# DM1097_RIGHT_OV9282.net
KiCad netlist of a schematic drawn in Altium Designer
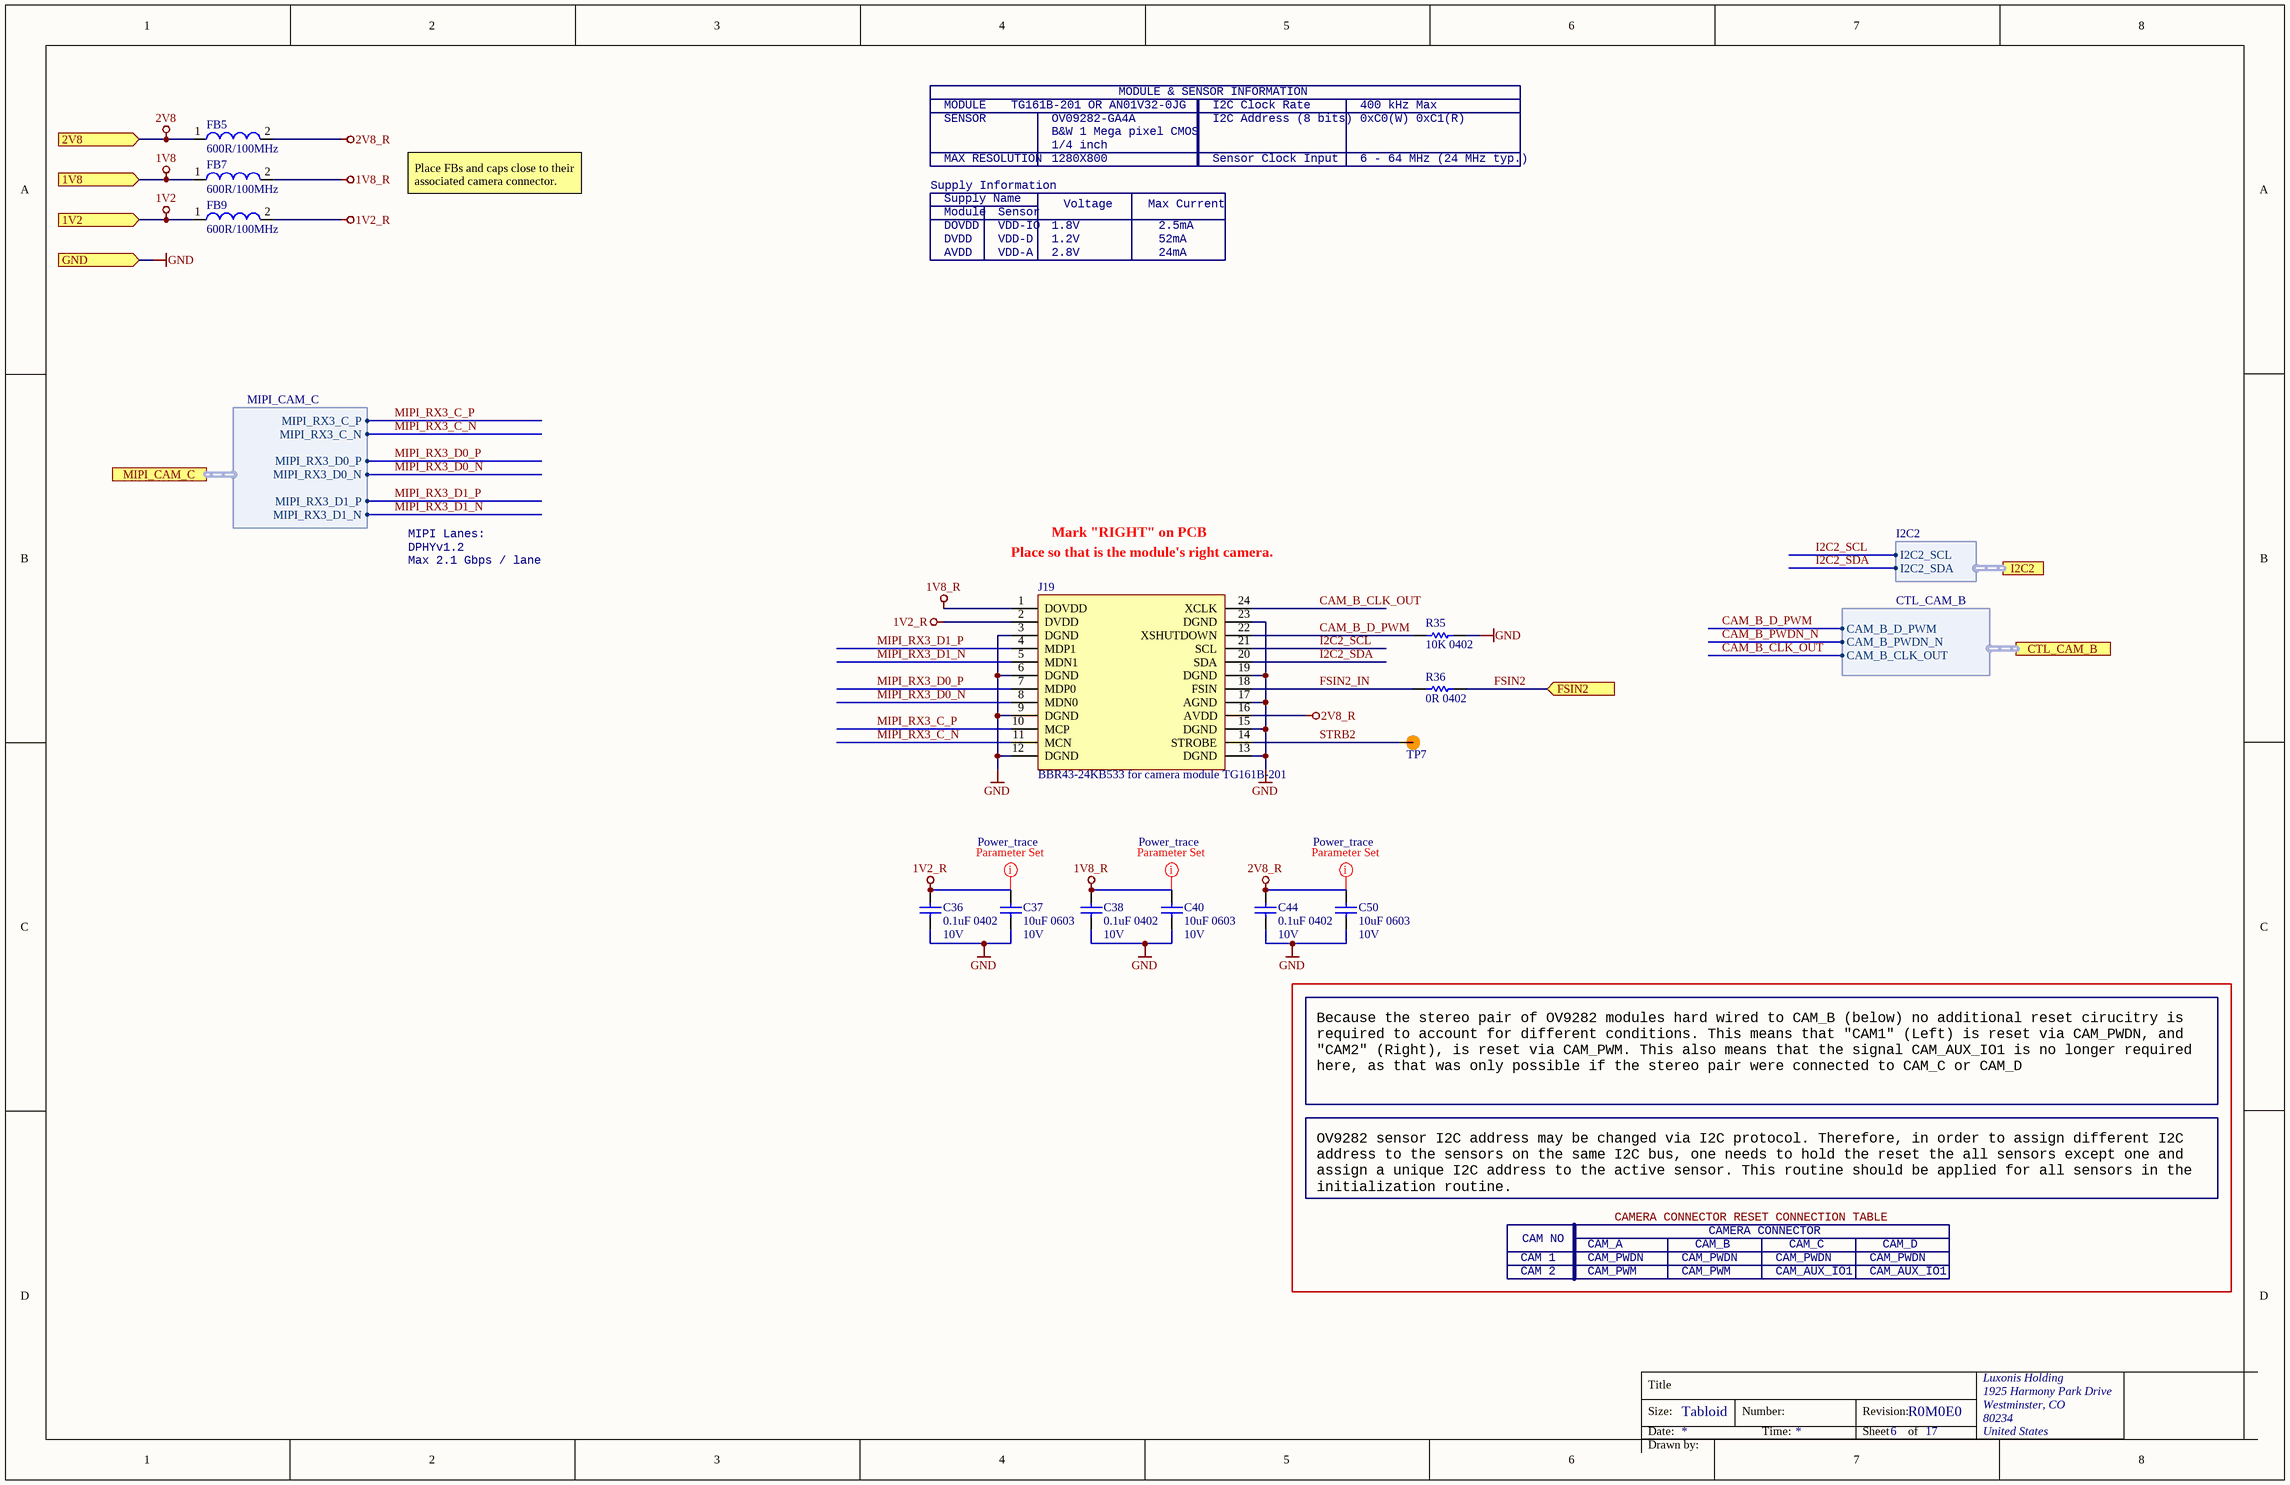
[diagram p0: DM1097_RIGHT_OV9282.SchDoc]

(export (version "E")
  (design (tool "Eeschema 10.0.6"))
  (components
    (comp (ref "C36")
      (value "0.1uF 0402")
      (footprint "CAP_Altium_Vault_Generic:CAPC0402(1005)70_N")
      (description "CAP CER 0.1UF 10V X7R 0402 5%")
      (fields (field (name "TOLERANCE") "5%") (field (name "VOLTAGE RATING") "10V"))
      (libsource (lib "LuxonisMaster") (part "GRM155R71A104JA01D"))
    )
    (comp (ref "C37")
      (value "10uF 0603")
      (footprint "CAP_Altium_Vault_Generic:CAPC0603(1608)100_N")
      (description "CAP CER 10UF 10V X5R 0603 20%")
      (fields (field (name "TOLERANCE") "20%") (field (name "VOLTAGE RATING") "10V"))
      (libsource (lib "LuxonisMaster") (part "GRM188R61A106ME69D"))
    )
    (comp (ref "C38")
      (value "0.1uF 0402")
      (footprint "CAP_Altium_Vault_Generic:CAPC0402(1005)70_N")
      (description "CAP CER 0.1UF 10V X7R 0402 5%")
      (fields (field (name "TOLERANCE") "5%") (field (name "VOLTAGE RATING") "10V"))
      (libsource (lib "LuxonisMaster") (part "GRM155R71A104JA01D"))
    )
    (comp (ref "C40")
      (value "10uF 0603")
      (footprint "CAP_Altium_Vault_Generic:CAPC0603(1608)100_N")
      (description "CAP CER 10UF 10V X5R 0603 20%")
      (fields (field (name "TOLERANCE") "20%") (field (name "VOLTAGE RATING") "10V"))
      (libsource (lib "LuxonisMaster") (part "GRM188R61A106ME69D"))
    )
    (comp (ref "C44")
      (value "0.1uF 0402")
      (footprint "CAP_Altium_Vault_Generic:CAPC0402(1005)70_N")
      (description "CAP CER 0.1UF 10V X7R 0402 5%")
      (fields (field (name "TOLERANCE") "5%") (field (name "VOLTAGE RATING") "10V"))
      (libsource (lib "LuxonisMaster") (part "GRM155R71A104JA01D"))
    )
    (comp (ref "C50")
      (value "10uF 0603")
      (footprint "CAP_Altium_Vault_Generic:CAPC0603(1608)100_N")
      (description "CAP CER 10UF 10V X5R 0603 20%")
      (fields (field (name "TOLERANCE") "20%") (field (name "VOLTAGE RATING") "10V"))
      (libsource (lib "LuxonisMaster") (part "GRM188R61A106ME69D"))
    )
    (comp (ref "FB5")
      (value "600R/100MHz")
      (footprint "LuxonisMaster:2508056017Y2")
      (description "FERRITE BEAD, 0.1OHM, 2A, 0805, 600R/100MHz")
      (fields (field (name "TOLERANCE") "25%"))
      (libsource (lib "LuxonisMaster") (part "2508056017Y2"))
    )
    (comp (ref "FB7")
      (value "600R/100MHz")
      (footprint "LuxonisMaster:2508056017Y2")
      (description "FERRITE BEAD, 0.1OHM, 2A, 0805, 600R/100MHz")
      (fields (field (name "TOLERANCE") "25%"))
      (libsource (lib "LuxonisMaster") (part "2508056017Y2"))
    )
    (comp (ref "FB9")
      (value "600R/100MHz")
      (footprint "LuxonisMaster:2508056017Y2")
      (description "FERRITE BEAD, 0.1OHM, 2A, 0805, 600R/100MHz")
      (fields (field (name "TOLERANCE") "25%"))
      (libsource (lib "LuxonisMaster") (part "2508056017Y2"))
    )
    (comp (ref "J19")
      (value "BBR43-24KB533 for camera module TG161B-201")
      (footprint "LuxonisMaster:TG161B-201_HD")
      (description "CONN 24 way, 2 row board to board connector SMD")
      (fields (field (name "MANUFACTURER") "ACON"))
      (libsource (lib "LuxonisMaster") (part "TG161B-201_Connector"))
    )
    (comp (ref "R35")
      (value "10K 0402")
      (footprint "RES_Altium_Vault_Generic:RESC0402(1005)_N")
      (fields (field (name "TOLERANCE") "1%"))
      (libsource (lib "LuxonisMaster") (part "RC0402FR-1310KL"))
    )
    (comp (ref "R36")
      (value "0R 0402")
      (footprint "RES_Altium_Vault_Generic:RESC0402(1005)_N")
      (description "RES SMD 0 OHM JUMPER 1/16W 0402")
      (fields (field (name "TOLERANCE") "5%"))
      (libsource (lib "LuxonisMaster") (part "CRCW04020000Z0ED"))
    )
    (comp (ref "TP7")
      (value "TP100_200_NS")
      (footprint "LuxonisMaster:TP100_200_NS")
      (libsource (lib "LuxonisMaster") (part "TEST_POINT"))
    )
  )
  (nets
    (net (code "4") (name "/CAM_B_CLK_OUT") (class "Default")
      (node (ref "J19") (pin "24") (pinfunction "XCLK_24") (pintype "passive"))
    )
    (net (code "5") (name "/CAM_B_D_PWM") (class "Default")
      (node (ref "J19") (pin "22") (pinfunction "XSHUTDOWN_22") (pintype "passive"))
      (node (ref "R35") (pin "1") (pinfunction "1_1") (pintype "passive"))
    )
    (net (code "7") (name "/FSIN2") (class "Default")
      (node (ref "R36") (pin "2") (pinfunction "2_2") (pintype "passive"))
    )
    (net (code "8") (name "/FSIN2_IN") (class "Default")
      (node (ref "J19") (pin "18") (pinfunction "FSIN_18") (pintype "passive"))
      (node (ref "R36") (pin "1") (pinfunction "1_1") (pintype "passive"))
    )
    (net (code "9") (name "/I2C2_SCL") (class "Default")
      (node (ref "J19") (pin "21") (pinfunction "SCL_21") (pintype "passive"))
    )
    (net (code "10") (name "/I2C2_SDA") (class "Default")
      (node (ref "J19") (pin "20") (pinfunction "SDA_20") (pintype "passive"))
    )
    (net (code "11") (name "/MIPI_RX3_C_N") (class "Default")
      (node (ref "J19") (pin "11") (pinfunction "MCN_11") (pintype "passive"))
    )
    (net (code "12") (name "/MIPI_RX3_C_P") (class "Default")
      (node (ref "J19") (pin "10") (pinfunction "MCP_10") (pintype "passive"))
    )
    (net (code "13") (name "/MIPI_RX3_D0_N") (class "Default")
      (node (ref "J19") (pin "8") (pinfunction "MDN0_8") (pintype "passive"))
    )
    (net (code "14") (name "/MIPI_RX3_D0_P") (class "Default")
      (node (ref "J19") (pin "7") (pinfunction "MDP0_7") (pintype "passive"))
    )
    (net (code "15") (name "/MIPI_RX3_D1_N") (class "Default")
      (node (ref "J19") (pin "5") (pinfunction "MDN1_5") (pintype "passive"))
    )
    (net (code "16") (name "/MIPI_RX3_D1_P") (class "Default")
      (node (ref "J19") (pin "4") (pinfunction "MDP1_4") (pintype "passive"))
    )
    (net (code "17") (name "/STRB2") (class "Default")
      (node (ref "J19") (pin "14") (pinfunction "STROBE_14") (pintype "passive"))
      (node (ref "TP7") (pin "1") (pintype "passive"))
    )
    (net (code "21") (name "1V2") (class "Default")
      (node (ref "FB9") (pin "1") (pinfunction "1_1") (pintype "passive"))
    )
    (net (code "22") (name "1V2_R") (class "Default")
      (node (ref "C36") (pin "2") (pinfunction "2_2") (pintype "passive"))
      (node (ref "C37") (pin "2") (pinfunction "2_2") (pintype "passive"))
      (node (ref "FB9") (pin "2") (pinfunction "2_2") (pintype "passive"))
      (node (ref "J19") (pin "2") (pinfunction "DVDD_2") (pintype "passive"))
    )
    (net (code "23") (name "1V8") (class "Default")
      (node (ref "FB7") (pin "1") (pinfunction "1_1") (pintype "passive"))
    )
    (net (code "24") (name "1V8_R") (class "Default")
      (node (ref "C38") (pin "2") (pinfunction "2_2") (pintype "passive"))
      (node (ref "C40") (pin "2") (pinfunction "2_2") (pintype "passive"))
      (node (ref "FB7") (pin "2") (pinfunction "2_2") (pintype "passive"))
      (node (ref "J19") (pin "1") (pinfunction "DOVDD_1") (pintype "passive"))
    )
    (net (code "25") (name "2V8") (class "Default")
      (node (ref "FB5") (pin "1") (pinfunction "1_1") (pintype "passive"))
    )
    (net (code "26") (name "2V8_R") (class "Default")
      (node (ref "C44") (pin "2") (pinfunction "2_2") (pintype "passive"))
      (node (ref "C50") (pin "2") (pinfunction "2_2") (pintype "passive"))
      (node (ref "FB5") (pin "2") (pinfunction "2_2") (pintype "passive"))
      (node (ref "J19") (pin "16") (pinfunction "AVDD_16") (pintype "passive"))
    )
    (net (code "27") (name "GND") (class "Default")
      (node (ref "C36") (pin "1") (pinfunction "1_1") (pintype "passive"))
      (node (ref "C37") (pin "1") (pinfunction "1_1") (pintype "passive"))
      (node (ref "C38") (pin "1") (pinfunction "1_1") (pintype "passive"))
      (node (ref "C40") (pin "1") (pinfunction "1_1") (pintype "passive"))
      (node (ref "C44") (pin "1") (pinfunction "1_1") (pintype "passive"))
      (node (ref "C50") (pin "1") (pinfunction "1_1") (pintype "passive"))
      (node (ref "J19") (pin "12") (pinfunction "DGND_12") (pintype "passive"))
      (node (ref "J19") (pin "13") (pinfunction "DGND_13") (pintype "passive"))
      (node (ref "J19") (pin "15") (pinfunction "DGND_15") (pintype "passive"))
      (node (ref "J19") (pin "17") (pinfunction "AGND_17") (pintype "passive"))
      (node (ref "J19") (pin "19") (pinfunction "DGND_19") (pintype "passive"))
      (node (ref "J19") (pin "23") (pinfunction "DGND_23") (pintype "passive"))
      (node (ref "J19") (pin "3") (pinfunction "DGND_3") (pintype "passive"))
      (node (ref "J19") (pin "6") (pinfunction "DGND_6") (pintype "passive"))
      (node (ref "J19") (pin "9") (pinfunction "DGND_9") (pintype "passive"))
      (node (ref "R35") (pin "2") (pinfunction "2_2") (pintype "passive"))
    )
  )
)
